# P05_BCS1_Ethernet.net
KiCad netlist of a schematic drawn in Altium Designer
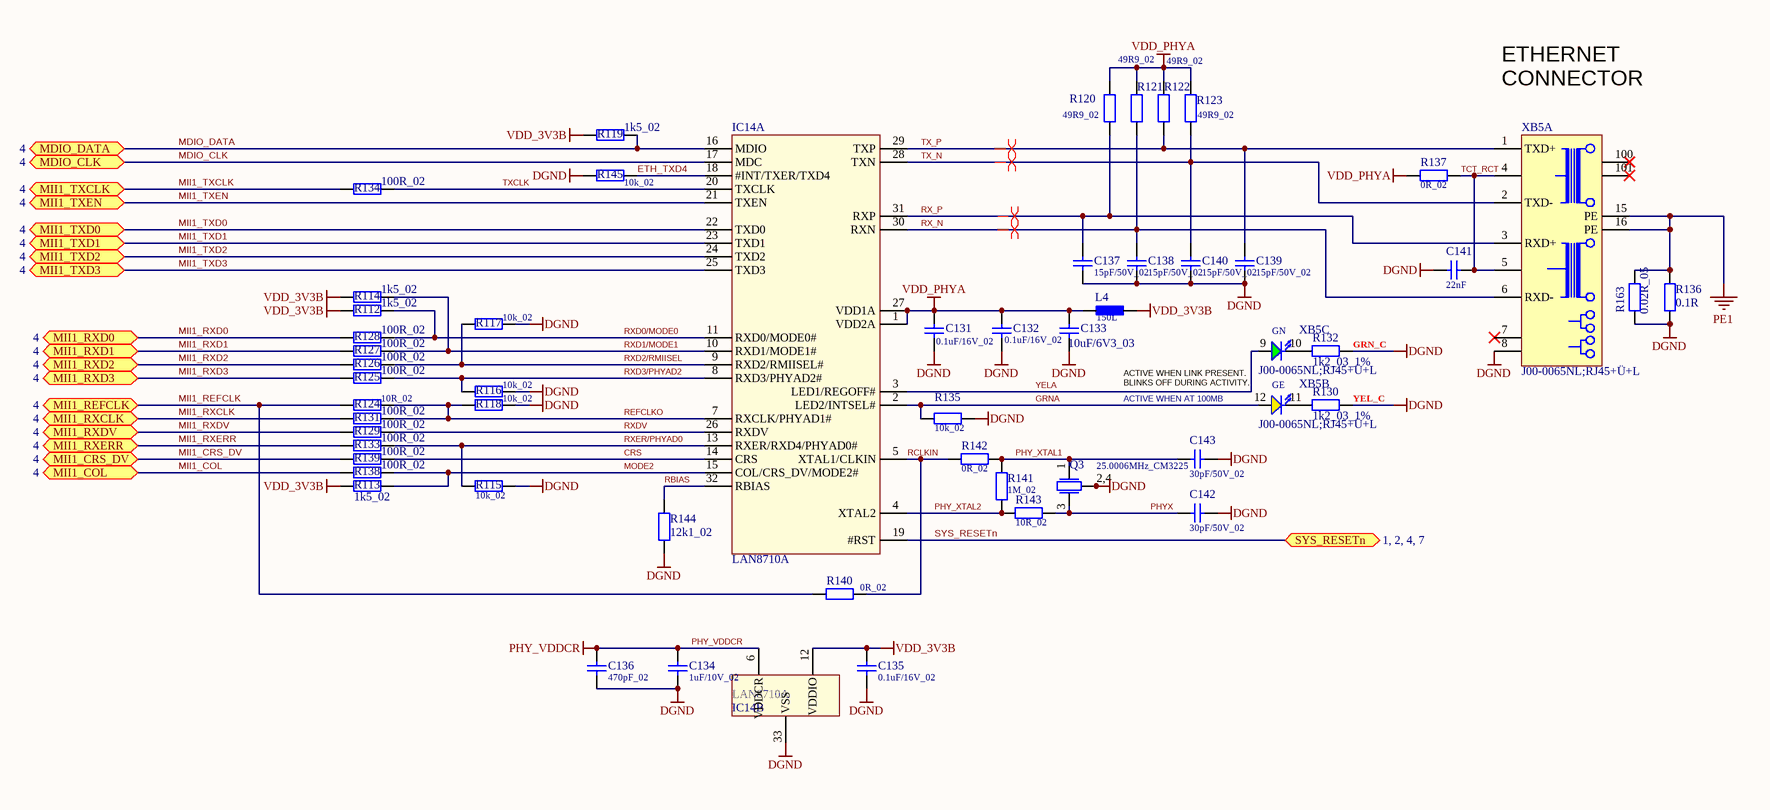
[diagram p0: P05_BCS1_Ethernet.SchDoc]

(export (version "E")
  (design (tool "Eeschema 10.0.6"))
  (components
    (comp (ref "C131")
      (value "0.1uF/16V_02")
      (footprint "CC1005-0402")
      (description "Capacitor 0402 16V Y5V")
      (libsource (lib "*") (part "C0.1uF/16V_02"))
    )
    (comp (ref "C132")
      (value "0.1uF/16V_02")
      (footprint "CC1005-0402")
      (description "Capacitor 0402 16V Y5V")
      (libsource (lib "*") (part "C0.1uF/16V_02"))
    )
    (comp (ref "C133")
      (value "10uF/6V3_03")
      (footprint "CC1608-0603")
      (description "Capacitor 0603 6V3; 10%, X5R")
      (libsource (lib "*") (part "C10uF/6V3_03"))
    )
    (comp (ref "C134")
      (value "1uF/10V_02")
      (footprint "CC1005-0402")
      (description "Capacitor 0402 10V, X5R")
      (libsource (lib "*") (part "C1uF/10V_02"))
    )
    (comp (ref "C135")
      (value "0.1uF/16V_02")
      (footprint "CC1005-0402")
      (description "Capacitor 0402 16V Y5V")
      (libsource (lib "*") (part "C0.1uF/16V_02"))
    )
    (comp (ref "C136")
      (value "470pF_02")
      (footprint "CC1005-0402")
      (description "Capacitor 0402; 50V X7R")
      (libsource (lib "*") (part "C470pF_02"))
    )
    (comp (ref "C137")
      (value "15pF/50V_02")
      (footprint "CC1005-0402")
      (description "Capacitor 0402; 50V")
      (libsource (lib "*") (part "C15pF/50V_02"))
    )
    (comp (ref "C138")
      (value "15pF/50V_02")
      (footprint "CC1005-0402")
      (description "Capacitor 0402; 50V")
      (libsource (lib "*") (part "C15pF/50V_02"))
    )
    (comp (ref "C139")
      (value "15pF/50V_02")
      (footprint "CC1005-0402")
      (description "Capacitor 0402; 50V")
      (libsource (lib "*") (part "C15pF/50V_02"))
    )
    (comp (ref "C140")
      (value "15pF/50V_02")
      (footprint "CC1005-0402")
      (description "Capacitor 0402; 50V")
      (libsource (lib "*") (part "C15pF/50V_02"))
    )
    (comp (ref "C141")
      (value "22nF")
      (footprint "CC2012-0805")
      (description "Capacitor 0805; 50V; 10%")
      (libsource (lib "*") (part "C22nF"))
    )
    (comp (ref "C142")
      (value "30pF/50V_02")
      (footprint "CC1005-0402")
      (description "Capacitor 0402 50V Y5V")
      (libsource (lib "*") (part "C30pF/16V_02"))
    )
    (comp (ref "C143")
      (value "30pF/50V_02")
      (footprint "CC1005-0402")
      (description "Capacitor 0402 50V Y5V")
      (libsource (lib "*") (part "C30pF/16V_02"))
    )
    (comp (ref "IC14")
      (value "LAN8710A")
      (footprint "QFN32+EP")
      (description "Small Footprint MII/RMII 10/100 Ethernet  Transceiver with HP Auto-MDIX and  flexPWR® Technology")
      (libsource (lib "") (part "ICLAN8710A_1"))
    )
    (comp (ref "L4")
      (value "150L")
      (footprint "CR2012-0805")
      (description "Inductor 120 Ohm Ferrite 0805, 800mA")
      (libsource (lib "*") (part "L150 Ohm Ferrite"))
    )
    (comp (ref "Q3")
      (value "25.0006MHz_CM3225")
      (footprint "QUARZ CM3225")
      (description "Quarz 25.0006MHz; CM3225")
      (libsource (lib "*") (part "Q25.0006MHz_CM3225"))
    )
    (comp (ref "R112")
      (value "1k5_02")
      (footprint "CR1005-0402")
      (description "Resistor 0402 1/16W 1%")
      (libsource (lib "*") (part "R1k5_02"))
    )
    (comp (ref "R113")
      (value "1k5_02")
      (footprint "CR1005-0402")
      (description "Resistor 0402 1/16W 1%")
      (libsource (lib "") (part "R1k5_02_1"))
    )
    (comp (ref "R114")
      (value "1k5_02")
      (footprint "CR1005-0402")
      (description "Resistor 0402 1/16W 1%")
      (libsource (lib "*") (part "R1k5_02"))
    )
    (comp (ref "R115")
      (value "10k_02")
      (footprint "CR1005-0402")
      (description "Resistor 0402")
      (libsource (lib "*") (part "R10k_02"))
    )
    (comp (ref "R116")
      (value "10k_02")
      (footprint "CR1005-0402")
      (description "Resistor 0402")
      (libsource (lib "*") (part "R10k_02"))
    )
    (comp (ref "R117")
      (value "10k_02")
      (footprint "CR1005-0402")
      (description "Resistor 0402")
      (libsource (lib "*") (part "R10k_02"))
    )
    (comp (ref "R118")
      (value "10k_02")
      (footprint "CR1005-0402")
      (description "Resistor 0402")
      (libsource (lib "*") (part "R10k_02"))
    )
    (comp (ref "R119")
      (value "1k5_02")
      (footprint "CR1005-0402")
      (description "Resistor 0402 1/16W 1%")
      (libsource (lib "*") (part "R1k5_02"))
    )
    (comp (ref "R120")
      (value "49R9_02")
      (footprint "CR1005-0402")
      (description "Resistor 0402")
      (libsource (lib "*") (part "R49R9_02"))
    )
    (comp (ref "R121")
      (value "49R9_02")
      (footprint "CR1005-0402")
      (description "Resistor 0402")
      (libsource (lib "*") (part "R49R9_02"))
    )
    (comp (ref "R122")
      (value "49R9_02")
      (footprint "CR1005-0402")
      (description "Resistor 0402")
      (libsource (lib "*") (part "R49R9_02"))
    )
    (comp (ref "R123")
      (value "49R9_02")
      (footprint "CR1005-0402")
      (description "Resistor 0402")
      (libsource (lib "*") (part "R49R9_02"))
    )
    (comp (ref "R124")
      (value "10R_02")
      (footprint "CR1005-0402")
      (description "Resistor 0402")
      (libsource (lib "*") (part "R10R_02"))
    )
    (comp (ref "R125")
      (value "100R_02")
      (footprint "CR1005-0402")
      (description "Resistor 0402 1%")
      (libsource (lib "*") (part "R100R_02"))
    )
    (comp (ref "R126")
      (value "100R_02")
      (footprint "CR1005-0402")
      (description "Resistor 0402 1%")
      (libsource (lib "*") (part "R100R_02"))
    )
    (comp (ref "R127")
      (value "100R_02")
      (footprint "CR1005-0402")
      (description "Resistor 0402 1%")
      (libsource (lib "*") (part "R100R_02"))
    )
    (comp (ref "R128")
      (value "100R_02")
      (footprint "CR1005-0402")
      (description "Resistor 0402 1%")
      (libsource (lib "*") (part "R100R_02"))
    )
    (comp (ref "R129")
      (value "100R_02")
      (footprint "CR1005-0402")
      (description "Resistor 0402 1%")
      (libsource (lib "*") (part "R100R_02"))
    )
    (comp (ref "R130")
      (value "1k2_03_1%")
      (footprint "CR1608-0603")
      (description "Resistor 0603; 1% 1/16W")
      (libsource (lib "*") (part "R1k2_03_1%"))
    )
    (comp (ref "R131")
      (value "100R_02")
      (footprint "CR1005-0402")
      (description "Resistor 0402 1%")
      (libsource (lib "*") (part "R100R_02"))
    )
    (comp (ref "R132")
      (value "1k2_03_1%")
      (footprint "CR1608-0603")
      (description "Resistor 0603; 1% 1/16W")
      (libsource (lib "*") (part "R1k2_03_1%"))
    )
    (comp (ref "R133")
      (value "100R_02")
      (footprint "CR1005-0402")
      (description "Resistor 0402 1%")
      (libsource (lib "*") (part "R100R_02"))
    )
    (comp (ref "R134")
      (value "100R_02")
      (footprint "CR1005-0402")
      (description "Resistor 0402 1%")
      (libsource (lib "*") (part "R100R_02"))
    )
    (comp (ref "R135")
      (value "10k_02")
      (footprint "CR1005-0402")
      (description "Resistor 0402")
      (libsource (lib "*") (part "R10k_02"))
    )
    (comp (ref "R136")
      (value "0.1R")
      (footprint "CR3216-1206")
      (description "Resistor 1206; 1% 1/4W;")
      (libsource (lib "*") (part "R0.1R"))
    )
    (comp (ref "R137")
      (value "0R_02")
      (footprint "CR1005-0402")
      (description "Resistor 0402")
      (libsource (lib "") (part "R0R_02_1"))
    )
    (comp (ref "R138")
      (value "100R_02")
      (footprint "CR1005-0402")
      (description "Resistor 0402 1%")
      (libsource (lib "*") (part "R100R_02"))
    )
    (comp (ref "R139")
      (value "100R_02")
      (footprint "CR1005-0402")
      (description "Resistor 0402 1%")
      (libsource (lib "*") (part "R100R_02"))
    )
    (comp (ref "R140")
      (value "0R_02")
      (footprint "CR1005-0402")
      (description "Resistor 0402")
      (libsource (lib "*") (part "R0R_02"))
    )
    (comp (ref "R141")
      (value "1M_02")
      (footprint "CR1005-0402")
      (description "Resistor 0402")
      (libsource (lib "*") (part "R1M_02"))
    )
    (comp (ref "R142")
      (value "0R_02")
      (footprint "CR1005-0402")
      (description "Resistor 0402")
      (libsource (lib "*") (part "R0R_02"))
    )
    (comp (ref "R143")
      (value "10R_02")
      (footprint "CR1005-0402")
      (description "Resistor 0402")
      (libsource (lib "*") (part "R10R_02"))
    )
    (comp (ref "R144")
      (value "12k1_02")
      (footprint "CR1005-0402")
      (description "Resistor 0402; 1%")
      (libsource (lib "*") (part "R12k1_02"))
    )
    (comp (ref "R145")
      (value "10k_02")
      (footprint "CR1005-0402")
      (description "Resistor 0402")
      (libsource (lib "*") (part "R10k_02"))
    )
    (comp (ref "R163")
      (value "0.02R_05")
      (footprint "CR2012-0805")
      (description "Resistor Bauform 0805; 5% 1/4W;")
      (libsource (lib "*") (part "R0.02R_05"))
    )
    (comp (ref "XB5")
      (value "J00-0065NL;RJ45+Ü+L")
      (footprint "RJ45+Ü+L")
      (description "Buchse RJ45 mit Übertrager und LEDS")
      (libsource (lib "*") (part "XBRJ45-J00-0065_ML"))
    )
  )
  (nets
    (net (code "1") (name "/CRS") (class "Default")
      (node (ref "IC14") (pin "14") (pinfunction "CRS_14") (pintype "passive"))
      (node (ref "R139") (pin "2") (pinfunction "2_2") (pintype "passive"))
    )
    (net (code "2") (name "/ETH_TXD4") (class "Default")
      (node (ref "IC14") (pin "18") (pinfunction "#INT/TXER/TXD4_18") (pintype "passive"))
      (node (ref "R145") (pin "2") (pinfunction "2_2") (pintype "passive"))
    )
    (net (code "3") (name "/GRNA") (class "Default")
      (node (ref "IC14") (pin "2") (pinfunction "LED2/INTSEL#_2") (pintype "passive"))
      (node (ref "R135") (pin "1") (pinfunction "1_1") (pintype "passive"))
      (node (ref "XB5") (pin "12") (pinfunction "A_12") (pintype "passive"))
    )
    (net (code "4") (name "/MDIO_CLK") (class "Default")
      (node (ref "IC14") (pin "17") (pinfunction "MDC_17") (pintype "passive"))
    )
    (net (code "5") (name "/MDIO_DATA") (class "Default")
      (node (ref "IC14") (pin "16") (pinfunction "MDIO_16") (pintype "passive"))
      (node (ref "R119") (pin "1") (pinfunction "1_1") (pintype "passive"))
    )
    (net (code "6") (name "/MII1_COL") (class "Default")
      (node (ref "R138") (pin "1") (pinfunction "1_1") (pintype "passive"))
    )
    (net (code "7") (name "/MII1_CRS_DV") (class "Default")
      (node (ref "R139") (pin "1") (pinfunction "1_1") (pintype "passive"))
    )
    (net (code "8") (name "/MII1_REFCLK") (class "Default")
      (node (ref "R124") (pin "1") (pinfunction "1_1") (pintype "passive"))
      (node (ref "R140") (pin "1") (pinfunction "1_1") (pintype "passive"))
    )
    (net (code "9") (name "/MII1_RXCLK") (class "Default")
      (node (ref "R131") (pin "1") (pinfunction "1_1") (pintype "passive"))
    )
    (net (code "10") (name "/MII1_RXD0") (class "Default")
      (node (ref "R128") (pin "1") (pinfunction "1_1") (pintype "passive"))
    )
    (net (code "11") (name "/MII1_RXD1") (class "Default")
      (node (ref "R127") (pin "1") (pinfunction "1_1") (pintype "passive"))
    )
    (net (code "12") (name "/MII1_RXD2") (class "Default")
      (node (ref "R126") (pin "1") (pinfunction "1_1") (pintype "passive"))
    )
    (net (code "13") (name "/MII1_RXD3") (class "Default")
      (node (ref "R125") (pin "1") (pinfunction "1_1") (pintype "passive"))
    )
    (net (code "14") (name "/MII1_RXDV") (class "Default")
      (node (ref "R129") (pin "1") (pinfunction "1_1") (pintype "passive"))
    )
    (net (code "15") (name "/MII1_RXERR") (class "Default")
      (node (ref "R133") (pin "1") (pinfunction "1_1") (pintype "passive"))
    )
    (net (code "16") (name "/MII1_TXCLK") (class "Default")
      (node (ref "R134") (pin "1") (pinfunction "1_1") (pintype "passive"))
    )
    (net (code "17") (name "/MII1_TXD0") (class "Default")
      (node (ref "IC14") (pin "22") (pinfunction "TXD0_22") (pintype "passive"))
    )
    (net (code "18") (name "/MII1_TXD1") (class "Default")
      (node (ref "IC14") (pin "23") (pinfunction "TXD1_23") (pintype "passive"))
    )
    (net (code "19") (name "/MII1_TXD2") (class "Default")
      (node (ref "IC14") (pin "24") (pinfunction "TXD2_24") (pintype "passive"))
    )
    (net (code "20") (name "/MII1_TXD3") (class "Default")
      (node (ref "IC14") (pin "25") (pinfunction "TXD3_25") (pintype "passive"))
    )
    (net (code "21") (name "/MII1_TXEN") (class "Default")
      (node (ref "IC14") (pin "21") (pinfunction "TXEN_21") (pintype "passive"))
    )
    (net (code "22") (name "/MODE2") (class "Default")
      (node (ref "IC14") (pin "15") (pinfunction "COL/CRS_DV/MODE2#_15") (pintype "passive"))
      (node (ref "R113") (pin "2") (pinfunction "2_2") (pintype "passive"))
      (node (ref "R138") (pin "2") (pinfunction "2_2") (pintype "passive"))
    )
    (net (code "23") (name "/PHYX") (class "Default")
      (node (ref "C142") (pin "1") (pinfunction "1_1") (pintype "passive"))
      (node (ref "Q3") (pin "3") (pinfunction "X2_3") (pintype "passive"))
      (node (ref "R143") (pin "2") (pinfunction "2_2") (pintype "passive"))
    )
    (net (code "24") (name "/PHY_XTAL1") (class "Default")
      (node (ref "C143") (pin "1") (pinfunction "1_1") (pintype "passive"))
      (node (ref "Q3") (pin "1") (pinfunction "X1_1") (pintype "passive"))
      (node (ref "R141") (pin "1") (pinfunction "1_1") (pintype "passive"))
      (node (ref "R142") (pin "2") (pinfunction "2_2") (pintype "passive"))
    )
    (net (code "25") (name "/PHY_XTAL2") (class "Default")
      (node (ref "IC14") (pin "4") (pinfunction "XTAL2_4") (pintype "passive"))
      (node (ref "R141") (pin "2") (pinfunction "2_2") (pintype "passive"))
      (node (ref "R143") (pin "1") (pinfunction "1_1") (pintype "passive"))
    )
    (net (code "26") (name "/RBIAS") (class "Default")
      (node (ref "IC14") (pin "32") (pinfunction "RBIAS_32") (pintype "passive"))
      (node (ref "R144") (pin "1") (pinfunction "1_1") (pintype "passive"))
    )
    (net (code "27") (name "/RCLKIN") (class "Default")
      (node (ref "IC14") (pin "5") (pinfunction "XTAL1/CLKIN_5") (pintype "passive"))
      (node (ref "R140") (pin "2") (pinfunction "2_2") (pintype "passive"))
      (node (ref "R142") (pin "1") (pinfunction "1_1") (pintype "passive"))
    )
    (net (code "28") (name "/REFCLKO") (class "Default")
      (node (ref "IC14") (pin "7") (pinfunction "RXCLK/PHYAD1#_7") (pintype "passive"))
      (node (ref "R118") (pin "1") (pinfunction "1_1") (pintype "passive"))
      (node (ref "R124") (pin "2") (pinfunction "2_2") (pintype "passive"))
      (node (ref "R131") (pin "2") (pinfunction "2_2") (pintype "passive"))
    )
    (net (code "29") (name "/RXD0{slash}MODE0") (class "Default")
      (node (ref "IC14") (pin "11") (pinfunction "RXD0/MODE0#_11") (pintype "passive"))
      (node (ref "R112") (pin "1") (pinfunction "1_1") (pintype "passive"))
      (node (ref "R128") (pin "2") (pinfunction "2_2") (pintype "passive"))
    )
    (net (code "30") (name "/RXD1{slash}MODE1") (class "Default")
      (node (ref "IC14") (pin "10") (pinfunction "RXD1/MODE1#_10") (pintype "passive"))
      (node (ref "R114") (pin "1") (pinfunction "1_1") (pintype "passive"))
      (node (ref "R127") (pin "2") (pinfunction "2_2") (pintype "passive"))
    )
    (net (code "31") (name "/RXD2{slash}RMIISEL") (class "Default")
      (node (ref "IC14") (pin "9") (pinfunction "RXD2/RMIISEL#_9") (pintype "passive"))
      (node (ref "R117") (pin "1") (pinfunction "1_1") (pintype "passive"))
      (node (ref "R126") (pin "2") (pinfunction "2_2") (pintype "passive"))
    )
    (net (code "32") (name "/RXD3{slash}PHYAD2") (class "Default")
      (node (ref "IC14") (pin "8") (pinfunction "RXD3/PHYAD2#_8") (pintype "passive"))
      (node (ref "R116") (pin "1") (pinfunction "1_1") (pintype "passive"))
      (node (ref "R125") (pin "2") (pinfunction "2_2") (pintype "passive"))
    )
    (net (code "33") (name "/RXDV") (class "Default")
      (node (ref "IC14") (pin "26") (pinfunction "RXDV_26") (pintype "passive"))
      (node (ref "R129") (pin "2") (pinfunction "2_2") (pintype "passive"))
    )
    (net (code "34") (name "/RXER{slash}PHYAD0") (class "Default")
      (node (ref "IC14") (pin "13") (pinfunction "RXER/RXD4/PHYAD0#_13") (pintype "passive"))
      (node (ref "R115") (pin "1") (pinfunction "1_1") (pintype "passive"))
      (node (ref "R133") (pin "2") (pinfunction "2_2") (pintype "passive"))
    )
    (net (code "35") (name "/RX_N") (class "Default")
      (node (ref "C138") (pin "2") (pinfunction "2_2") (pintype "passive"))
      (node (ref "IC14") (pin "30") (pinfunction "RXN_30") (pintype "passive"))
      (node (ref "R121") (pin "2") (pinfunction "2_2") (pintype "passive"))
      (node (ref "XB5") (pin "6") (pinfunction "RXD-_6") (pintype "passive"))
    )
    (net (code "36") (name "/RX_P") (class "Default")
      (node (ref "C137") (pin "2") (pinfunction "2_2") (pintype "passive"))
      (node (ref "IC14") (pin "31") (pinfunction "RXP_31") (pintype "passive"))
      (node (ref "R120") (pin "2") (pinfunction "2_2") (pintype "passive"))
      (node (ref "XB5") (pin "3") (pinfunction "RXD+_3") (pintype "passive"))
    )
    (net (code "37") (name "/SYS_RESETn") (class "Default")
      (node (ref "IC14") (pin "19") (pinfunction "#RST_19") (pintype "passive"))
    )
    (net (code "38") (name "/TCT_RCT") (class "Default")
      (node (ref "C141") (pin "2") (pinfunction "2_2") (pintype "passive"))
      (node (ref "R137") (pin "1") (pinfunction "1_1") (pintype "passive"))
      (node (ref "XB5") (pin "4") (pinfunction "NC_4") (pintype "passive"))
      (node (ref "XB5") (pin "5") (pinfunction "NC_5") (pintype "passive"))
    )
    (net (code "39") (name "/TXCLK") (class "Default")
      (node (ref "IC14") (pin "20") (pinfunction "TXCLK_20") (pintype "passive"))
      (node (ref "R134") (pin "2") (pinfunction "2_2") (pintype "passive"))
    )
    (net (code "40") (name "/TX_N") (class "Default")
      (node (ref "C140") (pin "2") (pinfunction "2_2") (pintype "passive"))
      (node (ref "IC14") (pin "28") (pinfunction "TXN_28") (pintype "passive"))
      (node (ref "R123") (pin "2") (pinfunction "2_2") (pintype "passive"))
      (node (ref "XB5") (pin "2") (pinfunction "TXD-_2") (pintype "passive"))
    )
    (net (code "41") (name "/TX_P") (class "Default")
      (node (ref "C139") (pin "2") (pinfunction "2_2") (pintype "passive"))
      (node (ref "IC14") (pin "29") (pinfunction "TXP_29") (pintype "passive"))
      (node (ref "R122") (pin "2") (pinfunction "2_2") (pintype "passive"))
      (node (ref "XB5") (pin "1") (pinfunction "TXD+_1") (pintype "passive"))
    )
    (net (code "42") (name "/YELA") (class "Default")
      (node (ref "IC14") (pin "3") (pinfunction "LED1/REGOFF#_3") (pintype "passive"))
      (node (ref "XB5") (pin "9") (pinfunction "A_9") (pintype "passive"))
    )
    (net (code "43") (name "DGND") (class "Default")
      (node (ref "C131") (pin "1") (pinfunction "1_1") (pintype "passive"))
      (node (ref "C132") (pin "1") (pinfunction "1_1") (pintype "passive"))
      (node (ref "C133") (pin "1") (pinfunction "1_1") (pintype "passive"))
      (node (ref "C134") (pin "1") (pinfunction "1_1") (pintype "passive"))
      (node (ref "C135") (pin "2") (pinfunction "2_2") (pintype "passive"))
      (node (ref "C136") (pin "1") (pinfunction "1_1") (pintype "passive"))
      (node (ref "C137") (pin "1") (pinfunction "1_1") (pintype "passive"))
      (node (ref "C138") (pin "1") (pinfunction "1_1") (pintype "passive"))
      (node (ref "C139") (pin "1") (pinfunction "1_1") (pintype "passive"))
      (node (ref "C140") (pin "1") (pinfunction "1_1") (pintype "passive"))
      (node (ref "C141") (pin "1") (pinfunction "1_1") (pintype "passive"))
      (node (ref "C142") (pin "2") (pinfunction "2_2") (pintype "passive"))
      (node (ref "C143") (pin "2") (pinfunction "2_2") (pintype "passive"))
      (node (ref "IC14") (pin "33") (pinfunction "VSS_33") (pintype "passive"))
      (node (ref "Q3") (pin "2") (pinfunction "GND_2") (pintype "passive"))
      (node (ref "Q3") (pin "4") (pinfunction "GND_4") (pintype "passive"))
      (node (ref "R115") (pin "2") (pinfunction "2_2") (pintype "passive"))
      (node (ref "R116") (pin "2") (pinfunction "2_2") (pintype "passive"))
      (node (ref "R117") (pin "2") (pinfunction "2_2") (pintype "passive"))
      (node (ref "R118") (pin "2") (pinfunction "2_2") (pintype "passive"))
      (node (ref "R130") (pin "2") (pinfunction "2_2") (pintype "passive"))
      (node (ref "R132") (pin "2") (pinfunction "2_2") (pintype "passive"))
      (node (ref "R135") (pin "2") (pinfunction "2_2") (pintype "passive"))
      (node (ref "R136") (pin "1") (pinfunction "1_1") (pintype "passive"))
      (node (ref "R144") (pin "2") (pinfunction "2_2") (pintype "passive"))
      (node (ref "R145") (pin "1") (pinfunction "1_1") (pintype "passive"))
      (node (ref "R163") (pin "1") (pinfunction "1_1") (pintype "passive"))
      (node (ref "XB5") (pin "8") (pinfunction "NC_8") (pintype "passive"))
    )
    (net (code "44") (name "Net-(XB5B-K)") (class "Default")
      (node (ref "R130") (pin "1") (pinfunction "1_1") (pintype "passive"))
      (node (ref "XB5") (pin "11") (pinfunction "K_11") (pintype "passive"))
    )
    (net (code "45") (name "Net-(XB5C-K)") (class "Default")
      (node (ref "R132") (pin "1") (pinfunction "1_1") (pintype "passive"))
      (node (ref "XB5") (pin "10") (pinfunction "K_10") (pintype "passive"))
    )
    (net (code "46") (name "PE1") (class "Default")
      (node (ref "R136") (pin "2") (pinfunction "2_2") (pintype "passive"))
      (node (ref "R163") (pin "2") (pinfunction "2_2") (pintype "passive"))
      (node (ref "XB5") (pin "15") (pinfunction "PE_15") (pintype "passive"))
      (node (ref "XB5") (pin "16") (pinfunction "PE_16") (pintype "passive"))
    )
    (net (code "47") (name "PHY_VDDCR") (class "Default")
      (node (ref "C134") (pin "2") (pinfunction "2_2") (pintype "passive"))
      (node (ref "C136") (pin "2") (pinfunction "2_2") (pintype "passive"))
      (node (ref "IC14") (pin "6") (pinfunction "VDDCR_6") (pintype "passive"))
    )
    (net (code "48") (name "VDD_3V3B") (class "Default")
      (node (ref "C135") (pin "1") (pinfunction "1_1") (pintype "passive"))
      (node (ref "IC14") (pin "12") (pinfunction "VDDIO_12") (pintype "passive"))
      (node (ref "L4") (pin "2") (pinfunction "2_2") (pintype "passive"))
      (node (ref "R112") (pin "2") (pinfunction "2_2") (pintype "passive"))
      (node (ref "R113") (pin "1") (pinfunction "1_1") (pintype "passive"))
      (node (ref "R114") (pin "2") (pinfunction "2_2") (pintype "passive"))
      (node (ref "R119") (pin "2") (pinfunction "2_2") (pintype "passive"))
    )
    (net (code "49") (name "VDD_PHYA") (class "Default")
      (node (ref "C131") (pin "2") (pinfunction "2_2") (pintype "passive"))
      (node (ref "C132") (pin "2") (pinfunction "2_2") (pintype "passive"))
      (node (ref "C133") (pin "2") (pinfunction "2_2") (pintype "passive"))
      (node (ref "IC14") (pin "1") (pinfunction "VDD2A_1") (pintype "passive"))
      (node (ref "IC14") (pin "27") (pinfunction "VDD1A_27") (pintype "passive"))
      (node (ref "L4") (pin "1") (pinfunction "1_1") (pintype "passive"))
      (node (ref "R120") (pin "1") (pinfunction "1_1") (pintype "passive"))
      (node (ref "R121") (pin "1") (pinfunction "1_1") (pintype "passive"))
      (node (ref "R122") (pin "1") (pinfunction "1_1") (pintype "passive"))
      (node (ref "R123") (pin "1") (pinfunction "1_1") (pintype "passive"))
      (node (ref "R137") (pin "2") (pinfunction "2_2") (pintype "passive"))
    )
    (net (code "50") (name "unconnected-(XB5-Pad100)") (class "Default")
      (node (ref "XB5") (pin "100") (pintype "passive+no_connect"))
    )
    (net (code "51") (name "unconnected-(XB5-Pad101)") (class "Default")
      (node (ref "XB5") (pin "101") (pintype "passive+no_connect"))
    )
    (net (code "52") (name "unconnected-(XB5A-NC-Pad7)") (class "Default")
      (node (ref "XB5") (pin "7") (pinfunction "NC_7") (pintype "passive+no_connect"))
    )
  )
)
